# servoreference.net
KiCad netlist of a schematic drawn in EAGLE
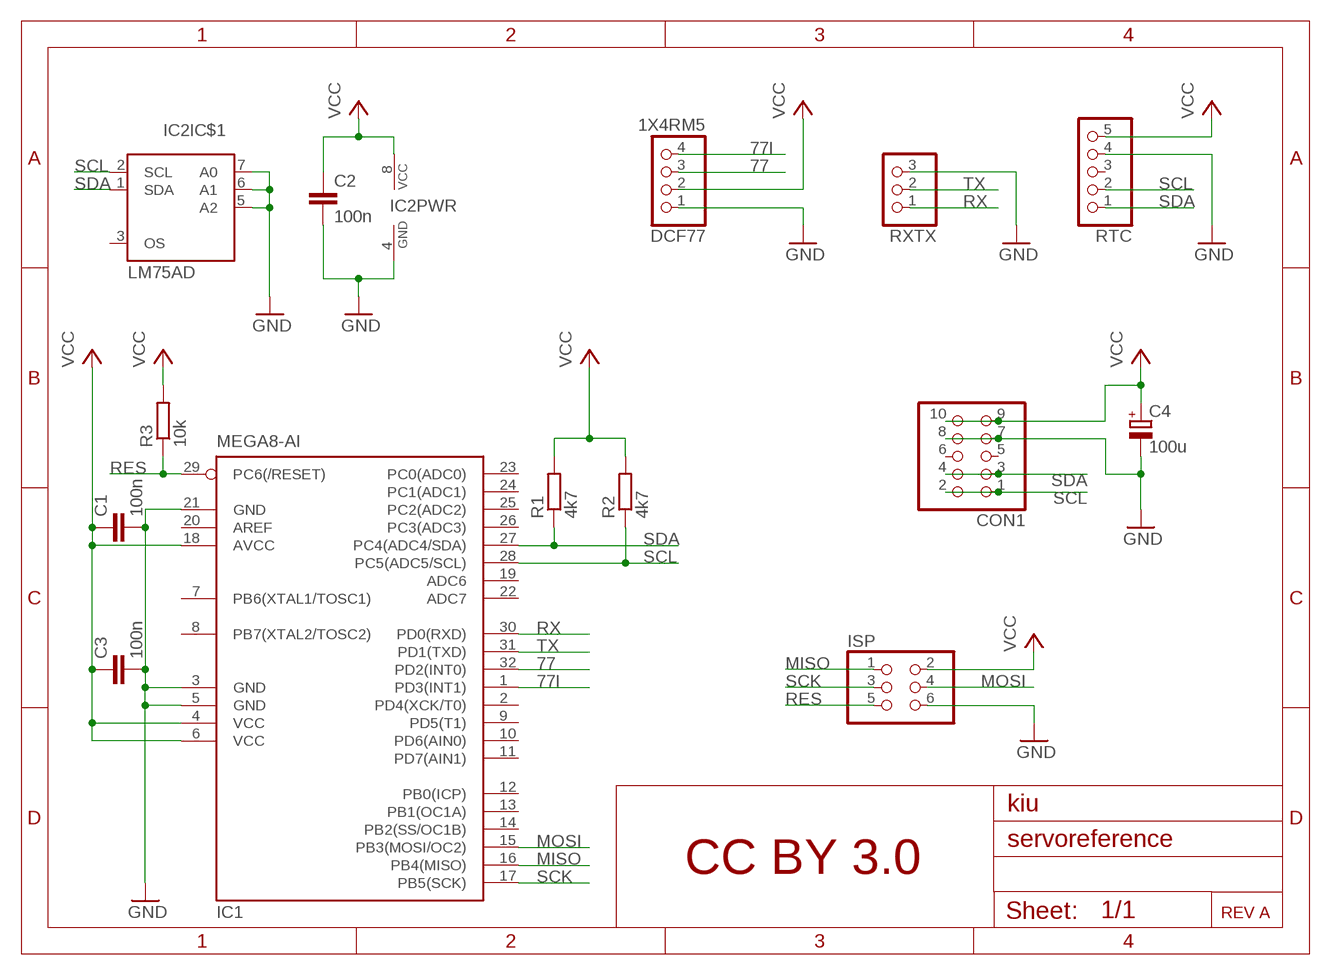
[diagram p0: schematic, sheet 1]

(export (version "E")
  (design (tool "Eeschema 10.0.6"))
  (components
    (comp (ref "C1")
      (value "100n")
      (footprint "eagle-import:C0805")
      (libsource (lib "eagle-import") (part "C-EUC0805"))
    )
    (comp (ref "C2")
      (value "100n")
      (footprint "eagle-import:C0805")
      (libsource (lib "eagle-import") (part "C-EUC0805"))
    )
    (comp (ref "C3")
      (value "100n")
      (footprint "eagle-import:C0805")
      (libsource (lib "eagle-import") (part "C-EUC0805"))
    )
    (comp (ref "C4")
      (value "100u")
      (footprint "eagle-import:153CLV-0505")
      (libsource (lib "eagle-import") (part "CPOL-EU153CLV-0505"))
    )
    (comp (ref "CON1")
      (value "PINHD-2X5")
      (footprint "eagle-import:2X05")
      (libsource (lib "eagle-import") (part "PINHD-2X5"))
    )
    (comp (ref "DCF77")
      (value "1X4RM5")
      (footprint "eagle-import:1X4RM5")
      (libsource (lib "eagle-import") (part "1X4RM5"))
    )
    (comp (ref "IC1")
      (value "MEGA8-AI")
      (footprint "eagle-import:TQFP32-08")
      (fields
        (field (name "MPN") "ATMEGA8-16AU")
        (field (name "MPN_1") "ATMEGA8-16AU")
        (field (name "OC_FARNELL") "9171371")
        (field (name "OC_NEWARK") "73M8863")
      )
      (libsource (lib "eagle-import") (part "MEGA8-AI"))
    )
    (comp (ref "IC2")
      (value "LM75AD")
      (footprint "eagle-import:SO08")
      (libsource (lib "eagle-import") (part "LM75AD"))
    )
    (comp (ref "ISP")
      (value "PINHD-2X3")
      (footprint "eagle-import:2X03")
      (libsource (lib "eagle-import") (part "PINHD-2X3"))
    )
    (comp (ref "R1")
      (value "4k7")
      (footprint "eagle-import:R0805")
      (libsource (lib "eagle-import") (part "R-EU_R0805"))
    )
    (comp (ref "R2")
      (value "4k7")
      (footprint "eagle-import:R0805")
      (libsource (lib "eagle-import") (part "R-EU_R0805"))
    )
    (comp (ref "R3")
      (value "10k")
      (footprint "eagle-import:R0805")
      (libsource (lib "eagle-import") (part "R-EU_R0805"))
    )
    (comp (ref "RTC")
      (value "PINHD-1X5")
      (footprint "eagle-import:1X05")
      (libsource (lib "eagle-import") (part "PINHD-1X5"))
    )
    (comp (ref "RXTX")
      (value "PINHD-1X3")
      (footprint "eagle-import:1X03")
      (libsource (lib "eagle-import") (part "PINHD-1X3"))
    )
  )
  (nets
    (net (code "1") (name "/77") (class "Default")
      (node (ref "DCF77") (pin "3") (pinfunction "3_3") (pintype "passive"))
      (node (ref "IC1") (pin "32") (pinfunction "PD2(INT0)_32") (pintype "bidirectional"))
    )
    (net (code "2") (name "/77I") (class "Default")
      (node (ref "DCF77") (pin "4") (pinfunction "4_4") (pintype "passive"))
      (node (ref "IC1") (pin "1") (pinfunction "PD3(INT1)_1") (pintype "bidirectional"))
    )
    (net (code "3") (name "/MISO") (class "Default")
      (node (ref "IC1") (pin "16") (pinfunction "PB4(MISO)_16") (pintype "bidirectional"))
      (node (ref "ISP") (pin "1") (pinfunction "1_1") (pintype "passive"))
    )
    (net (code "4") (name "/MOSI") (class "Default")
      (node (ref "IC1") (pin "15") (pinfunction "PB3(MOSI/OC2)_15") (pintype "bidirectional"))
      (node (ref "ISP") (pin "4") (pinfunction "4_4") (pintype "passive"))
    )
    (net (code "5") (name "/RES") (class "Default")
      (node (ref "IC1") (pin "29") (pinfunction "PC6(/RESET)_29") (pintype "bidirectional"))
      (node (ref "ISP") (pin "5") (pinfunction "5_5") (pintype "passive"))
      (node (ref "R3") (pin "1") (pinfunction "1_1") (pintype "passive"))
    )
    (net (code "6") (name "/RX") (class "Default")
      (node (ref "IC1") (pin "30") (pinfunction "PD0(RXD)_30") (pintype "bidirectional"))
      (node (ref "RXTX") (pin "1") (pinfunction "1_1") (pintype "passive"))
    )
    (net (code "7") (name "/SCK") (class "Default")
      (node (ref "IC1") (pin "17") (pinfunction "PB5(SCK)_17") (pintype "bidirectional"))
      (node (ref "ISP") (pin "3") (pinfunction "3_3") (pintype "passive"))
    )
    (net (code "8") (name "/SCL") (class "Default")
      (node (ref "CON1") (pin "1") (pinfunction "1_1") (pintype "passive"))
      (node (ref "CON1") (pin "2") (pinfunction "2_2") (pintype "passive"))
      (node (ref "IC1") (pin "28") (pinfunction "PC5(ADC5/SCL)_28") (pintype "bidirectional"))
      (node (ref "IC2") (pin "2") (pinfunction "SCL_2") (pintype "input"))
      (node (ref "R2") (pin "1") (pinfunction "1_1") (pintype "passive"))
      (node (ref "RTC") (pin "2") (pinfunction "2_2") (pintype "passive"))
    )
    (net (code "9") (name "/SDA") (class "Default")
      (node (ref "CON1") (pin "3") (pinfunction "3_3") (pintype "passive"))
      (node (ref "CON1") (pin "4") (pinfunction "4_4") (pintype "passive"))
      (node (ref "IC1") (pin "27") (pinfunction "PC4(ADC4/SDA)_27") (pintype "bidirectional"))
      (node (ref "IC2") (pin "1") (pinfunction "SDA_1") (pintype "bidirectional"))
      (node (ref "R1") (pin "1") (pinfunction "1_1") (pintype "passive"))
      (node (ref "RTC") (pin "1") (pinfunction "1_1") (pintype "passive"))
    )
    (net (code "10") (name "/TX") (class "Default")
      (node (ref "IC1") (pin "31") (pinfunction "PD1(TXD)_31") (pintype "bidirectional"))
      (node (ref "RXTX") (pin "2") (pinfunction "2_2") (pintype "passive"))
    )
    (net (code "11") (name "GND") (class "Default")
      (node (ref "C1") (pin "2") (pinfunction "2_2") (pintype "passive"))
      (node (ref "C2") (pin "2") (pinfunction "2_2") (pintype "passive"))
      (node (ref "C3") (pin "2") (pinfunction "2_2") (pintype "passive"))
      (node (ref "C4") (pin "-") (pinfunction "-_-") (pintype "passive"))
      (node (ref "CON1") (pin "7") (pinfunction "7_7") (pintype "passive"))
      (node (ref "CON1") (pin "8") (pinfunction "8_8") (pintype "passive"))
      (node (ref "DCF77") (pin "1") (pinfunction "1_1") (pintype "passive"))
      (node (ref "IC1") (pin "21") (pinfunction "GND_21") (pintype "power_in"))
      (node (ref "IC1") (pin "3") (pinfunction "GND_3") (pintype "power_in"))
      (node (ref "IC1") (pin "5") (pinfunction "GND_5") (pintype "power_in"))
      (node (ref "IC2") (pin "4") (pinfunction "GND_4") (pintype "power_in"))
      (node (ref "IC2") (pin "5") (pinfunction "A2_5") (pintype "input"))
      (node (ref "IC2") (pin "6") (pinfunction "A1_6") (pintype "input"))
      (node (ref "IC2") (pin "7") (pinfunction "A0_7") (pintype "input"))
      (node (ref "ISP") (pin "6") (pinfunction "6_6") (pintype "passive"))
      (node (ref "RTC") (pin "4") (pinfunction "4_4") (pintype "passive"))
      (node (ref "RXTX") (pin "3") (pinfunction "3_3") (pintype "passive"))
    )
    (net (code "12") (name "VCC") (class "Default")
      (node (ref "C1") (pin "1") (pinfunction "1_1") (pintype "passive"))
      (node (ref "C2") (pin "1") (pinfunction "1_1") (pintype "passive"))
      (node (ref "C3") (pin "1") (pinfunction "1_1") (pintype "passive"))
      (node (ref "C4") (pin "+") (pinfunction "+_+") (pintype "passive"))
      (node (ref "CON1") (pin "10") (pinfunction "10_10") (pintype "passive"))
      (node (ref "CON1") (pin "9") (pinfunction "9_9") (pintype "passive"))
      (node (ref "DCF77") (pin "2") (pinfunction "2_2") (pintype "passive"))
      (node (ref "IC1") (pin "18") (pinfunction "AVCC_18") (pintype "power_in"))
      (node (ref "IC1") (pin "4") (pinfunction "VCC_4") (pintype "power_in"))
      (node (ref "IC1") (pin "6") (pinfunction "VCC_6") (pintype "power_in"))
      (node (ref "IC2") (pin "8") (pinfunction "VCC_8") (pintype "power_in"))
      (node (ref "ISP") (pin "2") (pinfunction "2_2") (pintype "passive"))
      (node (ref "R1") (pin "2") (pinfunction "2_2") (pintype "passive"))
      (node (ref "R2") (pin "2") (pinfunction "2_2") (pintype "passive"))
      (node (ref "R3") (pin "2") (pinfunction "2_2") (pintype "passive"))
      (node (ref "RTC") (pin "5") (pinfunction "5_5") (pintype "passive"))
    )
    (net (code "13") (name "unconnected-(CON1-Pad5)") (class "Default")
      (node (ref "CON1") (pin "5") (pinfunction "5_5") (pintype "passive"))
    )
    (net (code "14") (name "unconnected-(CON1-Pad6)") (class "Default")
      (node (ref "CON1") (pin "6") (pinfunction "6_6") (pintype "passive"))
    )
    (net (code "15") (name "unconnected-(IC1-ADC6-Pad19)") (class "Default")
      (node (ref "IC1") (pin "19") (pinfunction "ADC6_19") (pintype "bidirectional"))
    )
    (net (code "16") (name "unconnected-(IC1-ADC7-Pad22)") (class "Default")
      (node (ref "IC1") (pin "22") (pinfunction "ADC7_22") (pintype "bidirectional"))
    )
    (net (code "17") (name "unconnected-(IC1-AREF-Pad20)") (class "Default")
      (node (ref "IC1") (pin "20") (pinfunction "AREF_20") (pintype "passive"))
    )
    (net (code "18") (name "unconnected-(IC1-PB0(ICP)-Pad12)") (class "Default")
      (node (ref "IC1") (pin "12") (pinfunction "PB0(ICP)_12") (pintype "bidirectional"))
    )
    (net (code "19") (name "unconnected-(IC1-PB1(OC1A)-Pad13)") (class "Default")
      (node (ref "IC1") (pin "13") (pinfunction "PB1(OC1A)_13") (pintype "bidirectional"))
    )
    (net (code "20") (name "unconnected-(IC1-PB2(SS{slash}OC1B)-Pad14)") (class "Default")
      (node (ref "IC1") (pin "14") (pinfunction "PB2(SS/OC1B)_14") (pintype "bidirectional"))
    )
    (net (code "21") (name "unconnected-(IC1-PB6(XTAL1{slash}TOSC1)-Pad7)") (class "Default")
      (node (ref "IC1") (pin "7") (pinfunction "PB6(XTAL1/TOSC1)_7") (pintype "bidirectional"))
    )
    (net (code "22") (name "unconnected-(IC1-PB7(XTAL2{slash}TOSC2)-Pad8)") (class "Default")
      (node (ref "IC1") (pin "8") (pinfunction "PB7(XTAL2/TOSC2)_8") (pintype "bidirectional"))
    )
    (net (code "23") (name "unconnected-(IC1-PC0(ADC0)-Pad23)") (class "Default")
      (node (ref "IC1") (pin "23") (pinfunction "PC0(ADC0)_23") (pintype "bidirectional"))
    )
    (net (code "24") (name "unconnected-(IC1-PC1(ADC1)-Pad24)") (class "Default")
      (node (ref "IC1") (pin "24") (pinfunction "PC1(ADC1)_24") (pintype "bidirectional"))
    )
    (net (code "25") (name "unconnected-(IC1-PC2(ADC2)-Pad25)") (class "Default")
      (node (ref "IC1") (pin "25") (pinfunction "PC2(ADC2)_25") (pintype "bidirectional"))
    )
    (net (code "26") (name "unconnected-(IC1-PC3(ADC3)-Pad26)") (class "Default")
      (node (ref "IC1") (pin "26") (pinfunction "PC3(ADC3)_26") (pintype "bidirectional"))
    )
    (net (code "27") (name "unconnected-(IC1-PD4(XCK{slash}T0)-Pad2)") (class "Default")
      (node (ref "IC1") (pin "2") (pinfunction "PD4(XCK/T0)_2") (pintype "bidirectional"))
    )
    (net (code "28") (name "unconnected-(IC1-PD5(T1)-Pad9)") (class "Default")
      (node (ref "IC1") (pin "9") (pinfunction "PD5(T1)_9") (pintype "bidirectional"))
    )
    (net (code "29") (name "unconnected-(IC1-PD6(AIN0)-Pad10)") (class "Default")
      (node (ref "IC1") (pin "10") (pinfunction "PD6(AIN0)_10") (pintype "bidirectional"))
    )
    (net (code "30") (name "unconnected-(IC1-PD7(AIN1)-Pad11)") (class "Default")
      (node (ref "IC1") (pin "11") (pinfunction "PD7(AIN1)_11") (pintype "bidirectional"))
    )
    (net (code "31") (name "unconnected-(IC2A-OS-Pad3)") (class "Default")
      (node (ref "IC2") (pin "3") (pinfunction "OS_3") (pintype "output"))
    )
    (net (code "32") (name "unconnected-(RTC-Pad3)") (class "Default")
      (node (ref "RTC") (pin "3") (pinfunction "3_3") (pintype "passive"))
    )
  )
)
